# Rocketometer2148_MPU9150.net
KiCad netlist of a schematic drawn in EAGLE
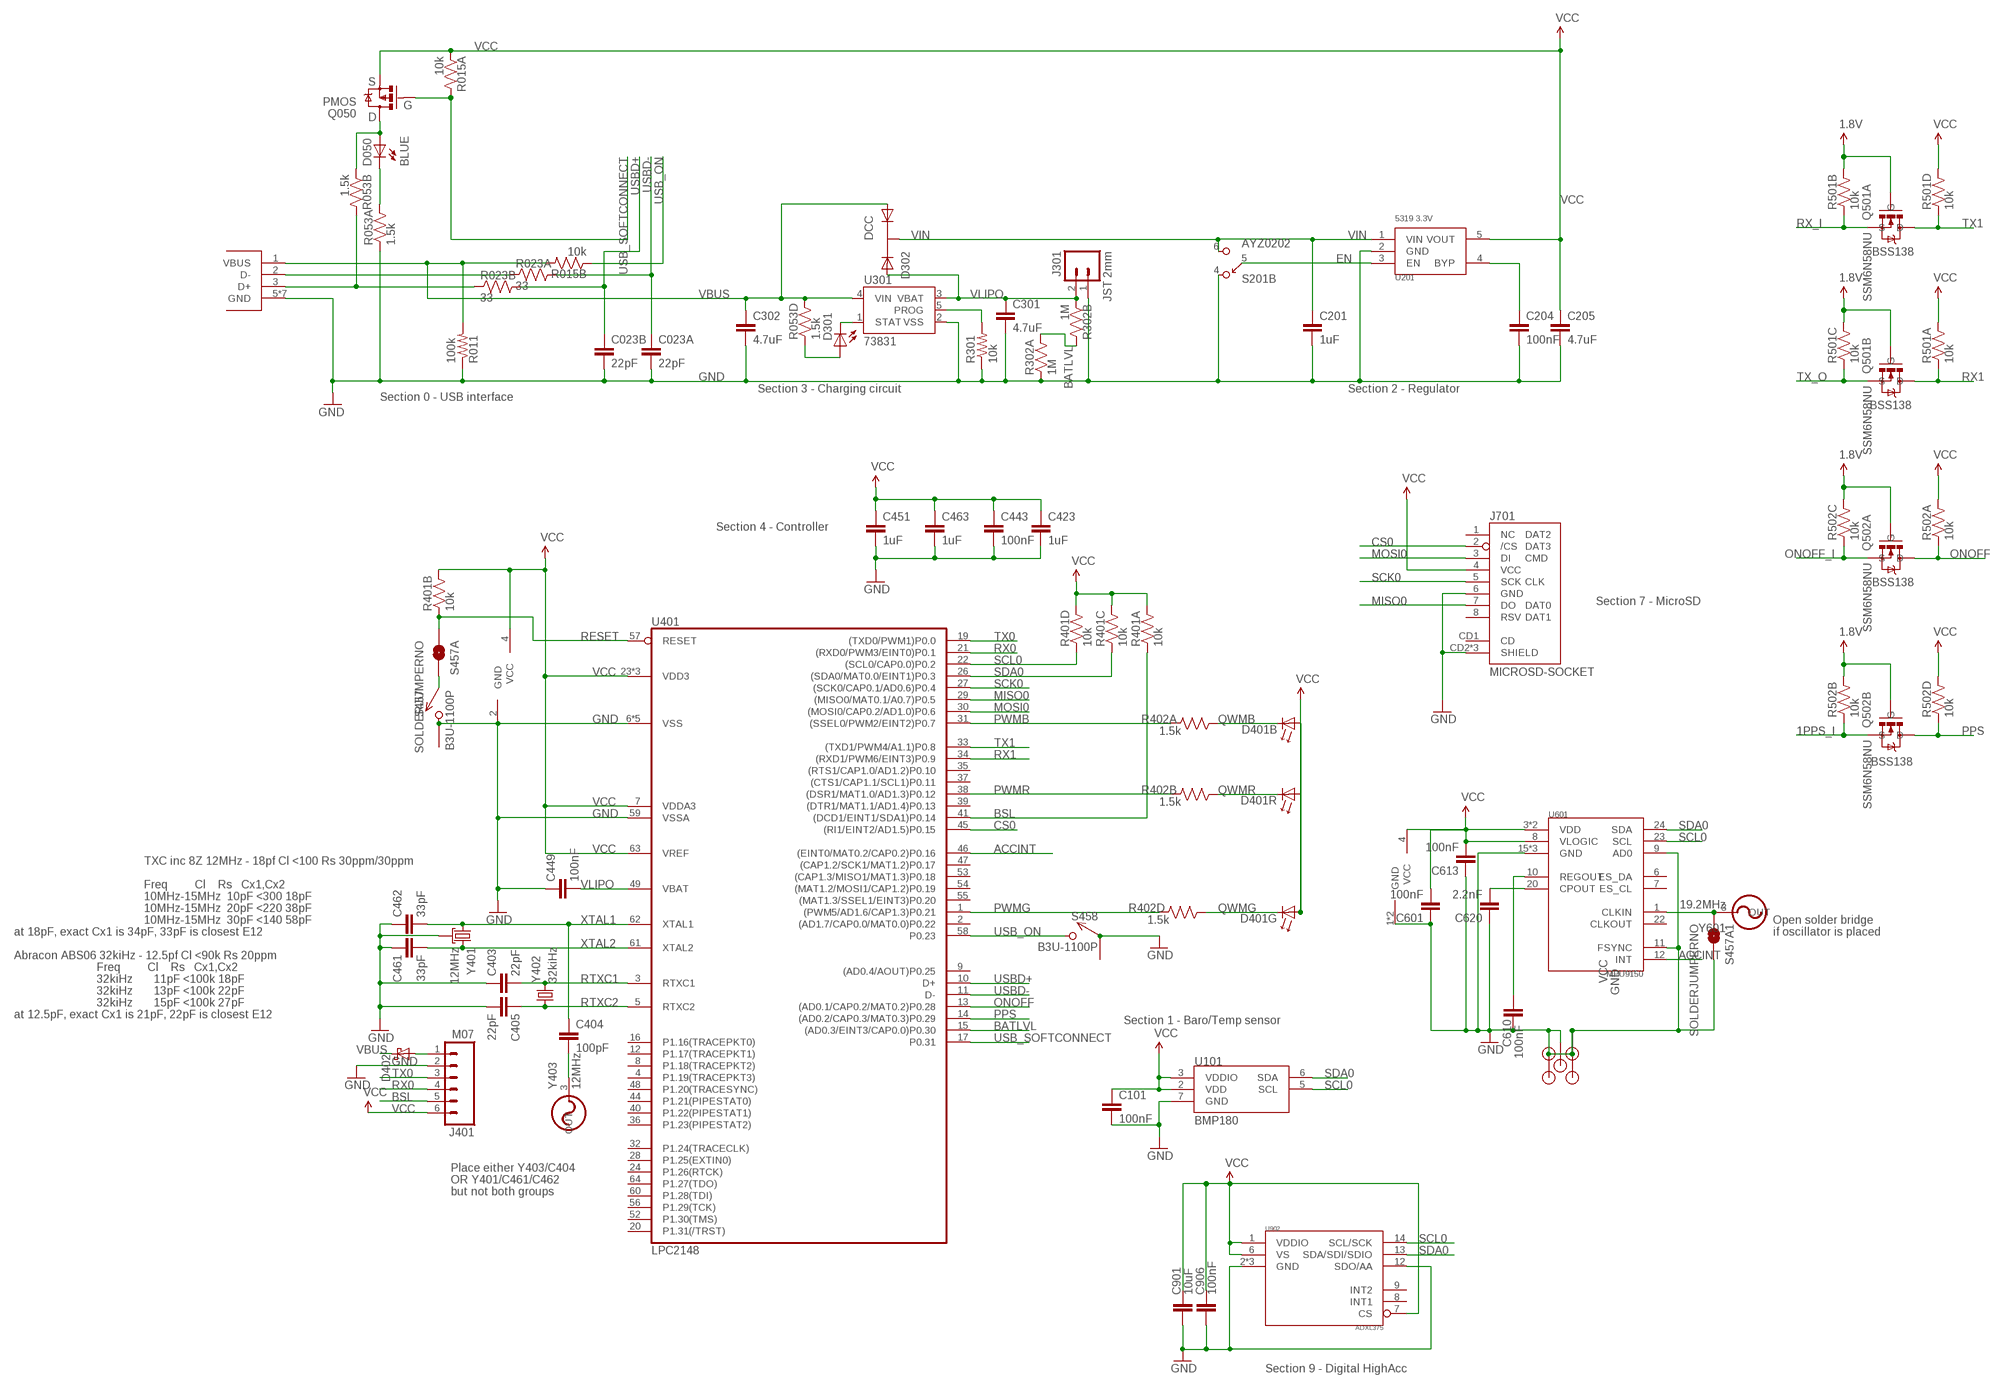
[diagram p0: schematic, sheet 1, part 1 of 2]
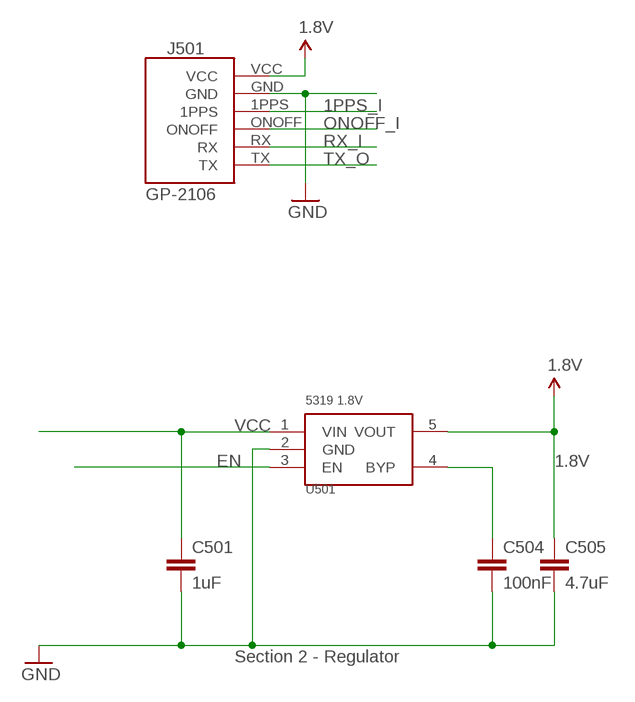
[diagram p1: schematic, sheet 1, part 2 of 2]

(export (version "E")
  (design (tool "Eeschema 10.0.6"))
  (components
    (comp (ref "C023")
      (value "22pF")
      (footprint "eagle-import:CKCM25")
      (fields (field (name "DIGIKEY") "445-1860-1-ND"))
      (libsource (lib "eagle-import") (part "CKCM25"))
    )
    (comp (ref "C101")
      (value "100nF")
      (footprint "eagle-import:0402-CAP")
      (libsource (lib "eagle-import") (part "CAP0402-CAP"))
    )
    (comp (ref "C201")
      (value "1uF")
      (footprint "eagle-import:0402-CAP")
      (libsource (lib "eagle-import") (part "CAP0402-CAP"))
    )
    (comp (ref "C204")
      (value "100nF")
      (footprint "eagle-import:0402-CAP")
      (libsource (lib "eagle-import") (part "CAP0402-CAP"))
    )
    (comp (ref "C205")
      (value "4.7uF")
      (footprint "eagle-import:0402-CAP")
      (libsource (lib "eagle-import") (part "CAP0402-CAP"))
    )
    (comp (ref "C301")
      (value "4.7uF")
      (footprint "eagle-import:0402-CAP")
      (libsource (lib "eagle-import") (part "CAP0402-CAP"))
    )
    (comp (ref "C302")
      (value "4.7uF")
      (footprint "eagle-import:0402-CAP")
      (libsource (lib "eagle-import") (part "CAP0402-CAP"))
    )
    (comp (ref "C403")
      (value "22pF")
      (footprint "eagle-import:0402-CAP")
      (libsource (lib "eagle-import") (part "CAP0402-CAP"))
    )
    (comp (ref "C404")
      (value "100pF")
      (footprint "eagle-import:0402-CAP")
      (libsource (lib "eagle-import") (part "CAP0402-CAP"))
    )
    (comp (ref "C405")
      (value "22pF")
      (footprint "eagle-import:0402-CAP")
      (libsource (lib "eagle-import") (part "CAP0402-CAP"))
    )
    (comp (ref "C423")
      (value "1uF")
      (footprint "eagle-import:0402-CAP")
      (libsource (lib "eagle-import") (part "CAP0402-CAP"))
    )
    (comp (ref "C443")
      (value "100nF")
      (footprint "eagle-import:0402-CAP")
      (libsource (lib "eagle-import") (part "CAP0402-CAP"))
    )
    (comp (ref "C449")
      (value "100nF")
      (footprint "eagle-import:0402-CAP")
      (libsource (lib "eagle-import") (part "CAP0402-CAP"))
    )
    (comp (ref "C451")
      (value "1uF")
      (footprint "eagle-import:0402-CAP")
      (libsource (lib "eagle-import") (part "CAP0402-CAP"))
    )
    (comp (ref "C461")
      (value "33pF")
      (footprint "eagle-import:0402-CAP")
      (libsource (lib "eagle-import") (part "CAP0402-CAP"))
    )
    (comp (ref "C462")
      (value "33pF")
      (footprint "eagle-import:0402-CAP")
      (libsource (lib "eagle-import") (part "CAP0402-CAP"))
    )
    (comp (ref "C463")
      (value "1uF")
      (footprint "eagle-import:0402-CAP")
      (libsource (lib "eagle-import") (part "CAP0402-CAP"))
    )
    (comp (ref "C501")
      (value "1uF")
      (footprint "eagle-import:0402-CAP")
      (libsource (lib "eagle-import") (part "CAP0402-CAP"))
    )
    (comp (ref "C504")
      (value "100nF")
      (footprint "eagle-import:0402-CAP")
      (libsource (lib "eagle-import") (part "CAP0402-CAP"))
    )
    (comp (ref "C505")
      (value "4.7uF")
      (footprint "eagle-import:0402-CAP")
      (libsource (lib "eagle-import") (part "CAP0402-CAP"))
    )
    (comp (ref "C601")
      (value "100nF")
      (footprint "eagle-import:0402-CAP")
      (libsource (lib "eagle-import") (part "CAP0402-CAP"))
    )
    (comp (ref "C610")
      (value "100nF")
      (footprint "eagle-import:0402-CAP")
      (libsource (lib "eagle-import") (part "CAP0402-CAP"))
    )
    (comp (ref "C613")
      (value "100nF")
      (footprint "eagle-import:0402-CAP")
      (libsource (lib "eagle-import") (part "CAP0402-CAP"))
    )
    (comp (ref "C620")
      (value "2.2nF")
      (footprint "eagle-import:0402-CAP")
      (libsource (lib "eagle-import") (part "CAP0402-CAP"))
    )
    (comp (ref "C901")
      (value "10uF")
      (footprint "eagle-import:0603-CAP")
      (libsource (lib "eagle-import") (part "CAP0603-CAP"))
    )
    (comp (ref "C906")
      (value "100nF")
      (footprint "eagle-import:0402-CAP")
      (libsource (lib "eagle-import") (part "SparkFun-Passives_CAP0402-CAP"))
    )
    (comp (ref "D050")
      (value "BLUE")
      (footprint "eagle-import:LED-0603")
      (libsource (lib "eagle-import") (part "LED0603"))
    )
    (comp (ref "D301")
      (value "YELLOW")
      (footprint "eagle-import:LED-0603")
      (libsource (lib "eagle-import") (part "LED0603"))
    )
    (comp (ref "D302")
      (value "DCC")
      (footprint "eagle-import:SOT-23-3")
      (libsource (lib "eagle-import") (part "PMEG2005CT"))
    )
    (comp (ref "D401")
      (value "SMLP36RGB2W(R)")
      (footprint "eagle-import:SMLP36")
      (fields (field (name "DIGIKEY") "846-1097-1-ND"))
      (libsource (lib "eagle-import") (part "SMLP36RGB2W(R)"))
    )
    (comp (ref "D402")
      (value "DIODE_SCHOTTKY")
      (footprint "eagle-import:D0603")
      (libsource (lib "eagle-import") (part "DIODE_SCHOTTKY"))
    )
    (comp (ref "J001")
      (value "USB_MICROB_JSTGCT")
      (footprint "eagle-import:USB_MICROB_3075")
      (libsource (lib "eagle-import") (part "USB_MICROB_JSTGCT"))
    )
    (comp (ref "J301")
      (value "JST 2mm")
      (footprint "eagle-import:JST-2-SMD")
      (libsource (lib "eagle-import") (part "M02-JST-2MM-SMT"))
    )
    (comp (ref "J401")
      (value "M07")
      (footprint "eagle-import:1X06")
      (libsource (lib "eagle-import") (part "M06SIP"))
    )
    (comp (ref "J501")
      (value "GP-2106")
      (footprint "eagle-import:GP-2106")
      (libsource (lib "eagle-import") (part "GP-2106"))
    )
    (comp (ref "J701")
      (value "MICROSD-SOCKET")
      (footprint "eagle-import:MICROSD-SOCKET-PP")
      (libsource (lib "eagle-import") (part "MICROSD-SOCKET"))
    )
    (comp (ref "JP1")
      (value "STANDOFF")
      (footprint "eagle-import:STANDOFF")
      (libsource (lib "eagle-import") (part "STANDOFF"))
    )
    (comp (ref "JP2")
      (value "STANDOFF")
      (footprint "eagle-import:STANDOFF")
      (libsource (lib "eagle-import") (part "STANDOFF"))
    )
    (comp (ref "JP3")
      (value "STANDOFF")
      (footprint "eagle-import:STANDOFF")
      (libsource (lib "eagle-import") (part "STANDOFF"))
    )
    (comp (ref "JP4")
      (value "STANDOFF")
      (footprint "eagle-import:STANDOFF")
      (libsource (lib "eagle-import") (part "STANDOFF"))
    )
    (comp (ref "JP5")
      (value "STANDOFF")
      (footprint "eagle-import:STANDOFF")
      (libsource (lib "eagle-import") (part "STANDOFF"))
    )
    (comp (ref "Q050")
      (value "PMOS")
      (footprint "eagle-import:SOT23-3")
      (libsource (lib "eagle-import") (part "MOSFET-PCHANNELSMD"))
    )
    (comp (ref "Q501")
      (value "SSM6N58NU")
      (footprint "eagle-import:UDFN6")
      (libsource (lib "eagle-import") (part "SSM6N58NU"))
    )
    (comp (ref "Q502")
      (value "SSM6N58NU")
      (footprint "eagle-import:UDFN6")
      (libsource (lib "eagle-import") (part "SSM6N58NU"))
    )
    (comp (ref "R011")
      (value "100k")
      (footprint "eagle-import:0402-RES")
      (libsource (lib "eagle-import") (part "RESISTOR0402-RES"))
    )
    (comp (ref "R015")
      (value "10k")
      (footprint "eagle-import:CRA02")
      (fields (field (name "DIGIKEY") "Y5103CT-ND"))
      (libsource (lib "eagle-import") (part "RP2EXB24V"))
    )
    (comp (ref "R023")
      (value "33")
      (footprint "eagle-import:CRA02")
      (libsource (lib "eagle-import") (part "RP2EXB24V"))
    )
    (comp (ref "R053")
      (value "1.5k")
      (footprint "eagle-import:CRA04")
      (fields (field (name "DIGIKEY") "CRA4S81.5KCT-ND"))
      (libsource (lib "eagle-import") (part "RP404"))
    )
    (comp (ref "R301")
      (value "10k")
      (footprint "eagle-import:0402-RES")
      (libsource (lib "eagle-import") (part "RESISTOR0402-RES"))
    )
    (comp (ref "R302")
      (value "1M")
      (footprint "eagle-import:CRA02")
      (libsource (lib "eagle-import") (part "RP2EXB24V"))
    )
    (comp (ref "R401")
      (value "10k")
      (footprint "eagle-import:CRA04")
      (fields (field (name "DIGIKEY") "CRA4S810KCT-ND"))
      (libsource (lib "eagle-import") (part "RP404"))
    )
    (comp (ref "R402")
      (value "1.5k")
      (footprint "eagle-import:CRA04")
      (fields (field (name "DIGIKEY") "CRA4S81.5KCT-ND"))
      (libsource (lib "eagle-import") (part "RP404"))
    )
    (comp (ref "R501")
      (value "10k")
      (footprint "eagle-import:CRA04")
      (fields (field (name "DIGIKEY") "CRA4S810KCT-ND"))
      (libsource (lib "eagle-import") (part "RP404"))
    )
    (comp (ref "R502")
      (value "10k")
      (footprint "eagle-import:CRA04")
      (fields (field (name "DIGIKEY") "CRA4S810KCT-ND"))
      (libsource (lib "eagle-import") (part "RP404"))
    )
    (comp (ref "S201")
      (value "AYZ0202")
      (footprint "eagle-import:AYZ0202")
      (libsource (lib "eagle-import") (part "AYZ0202"))
    )
    (comp (ref "S457")
      (value "B3U-1100P")
      (footprint "eagle-import:B3U-1100P")
      (fields (field (name "DIGIKEY") "SW1021CT-ND"))
      (libsource (lib "eagle-import") (part "B3U-1100P"))
    )
    (comp (ref "S457A")
      (value "SOLDERJUMPERNO")
      (footprint "eagle-import:SJ_2S-NO")
      (libsource (lib "eagle-import") (part "SOLDERJUMPERNO"))
    )
    (comp (ref "S457A1")
      (value "SOLDERJUMPERNO")
      (footprint "eagle-import:SJ_2S-NO")
      (libsource (lib "eagle-import") (part "SOLDERJUMPERNO"))
    )
    (comp (ref "S458")
      (value "B3U-1100P")
      (footprint "eagle-import:B3U-1100P")
      (fields (field (name "DIGIKEY") "SW1021CT-ND"))
      (libsource (lib "eagle-import") (part "B3U-1100P"))
    )
    (comp (ref "U101")
      (value "BMP180")
      (footprint "eagle-import:BMP180")
      (libsource (lib "eagle-import") (part "BMP180"))
    )
    (comp (ref "U201")
      (value "5319 3.3V")
      (footprint "eagle-import:SOT-23-5")
      (libsource (lib "eagle-import") (part "MIC5319D5"))
    )
    (comp (ref "U301")
      (value "73831")
      (footprint "eagle-import:SOT23-5")
      (libsource (lib "eagle-import") (part "MCP73831"))
    )
    (comp (ref "U401")
      (value "LPC2148")
      (footprint "eagle-import:LQFP64")
      (libsource (lib "eagle-import") (part "LPC2148"))
    )
    (comp (ref "U501")
      (value "5319 1.8V")
      (footprint "eagle-import:SOT-23-5")
      (libsource (lib "eagle-import") (part "MIC5319D5"))
    )
    (comp (ref "U601")
      (value "MPU9150")
      (footprint "eagle-import:LLGA24")
      (libsource (lib "eagle-import") (part "MPU9150"))
    )
    (comp (ref "U902")
      (value "ADXL375")
      (footprint "eagle-import:ADXL375")
      (libsource (lib "eagle-import") (part "ADXL375"))
    )
    (comp (ref "Y401")
      (value "12MHz")
      (footprint "eagle-import:CRYSTAL_SMD_2MM_2_5MM")
      (libsource (lib "eagle-import") (part "CX2520"))
    )
    (comp (ref "Y402")
      (value "32kiHz")
      (footprint "eagle-import:ABS06")
      (libsource (lib "eagle-import") (part "ABS06"))
    )
    (comp (ref "Y403")
      (value "12MHz")
      (footprint "eagle-import:CRYSTAL_SMD_5MM_3_2MM")
      (fields (field (name "DIGIKEY") "631-1068-1-ND"))
      (libsource (lib "eagle-import") (part "OSCILLATORE35MT"))
    )
    (comp (ref "Y601")
      (value "19.2MHz")
      (footprint "eagle-import:CRYSTAL_SMD_2MM_2_5MM")
      (libsource (lib "eagle-import") (part "OSCILLATORASDMB"))
    )
  )
  (nets
    (net (code "1") (name "/1PPS_I") (class "Default")
      (node (ref "J501") (pin "1PPS") (pinfunction "1PPS_1PPS") (pintype "bidirectional"))
      (node (ref "Q502") (pin "4") (pinfunction "S_4") (pintype "passive"))
      (node (ref "R502") (pin "2") (pinfunction "1_2") (pintype "passive"))
    )
    (net (code "2") (name "/ACCINT") (class "Default")
      (node (ref "U401") (pin "46") (pinfunction "(EINT0/MAT0.2/CAP0.2)P0.16_46") (pintype "bidirectional"))
      (node (ref "U601") (pin "12") (pinfunction "INT_12") (pintype "bidirectional"))
    )
    (net (code "3") (name "/BATLVL") (class "Default")
      (node (ref "R302") (pin "3") (pinfunction "2_3") (pintype "passive"))
      (node (ref "R302") (pin "4") (pinfunction "2_4") (pintype "passive"))
      (node (ref "U401") (pin "15") (pinfunction "(AD0.3/EINT3/CAP0.0)P0.30_15") (pintype "bidirectional"))
    )
    (net (code "4") (name "/BSL") (class "Default")
      (node (ref "J401") (pin "5") (pinfunction "5_5") (pintype "passive"))
      (node (ref "R401") (pin "1") (pinfunction "1_1") (pintype "passive"))
      (node (ref "U401") (pin "41") (pinfunction "(DCD1/EINT1/SDA1)P0.14_41") (pintype "bidirectional"))
    )
    (net (code "5") (name "/CS0") (class "Default")
      (node (ref "J701") (pin "2") (pinfunction "/CS_2") (pintype "bidirectional"))
      (node (ref "U401") (pin "45") (pinfunction "(RI1/EINT2/AD1.5)P0.15_45") (pintype "bidirectional"))
    )
    (net (code "6") (name "/EN") (class "Default")
      (node (ref "S201") (pin "5") (pinfunction "P$3_5") (pintype "bidirectional"))
      (node (ref "U201") (pin "3") (pinfunction "EN_3") (pintype "bidirectional"))
      (node (ref "U501") (pin "3") (pinfunction "EN_3") (pintype "bidirectional"))
    )
    (net (code "7") (name "/MISO0") (class "Default")
      (node (ref "J701") (pin "7") (pinfunction "DO_7") (pintype "bidirectional"))
      (node (ref "U401") (pin "29") (pinfunction "(MISO0/MAT0.1/A0.7)P0.5_29") (pintype "bidirectional"))
    )
    (net (code "8") (name "/MOSI0") (class "Default")
      (node (ref "J701") (pin "3") (pinfunction "DI_3") (pintype "bidirectional"))
      (node (ref "U401") (pin "30") (pinfunction "(MOSI0/CAP0.2/AD1.0)P0.6_30") (pintype "bidirectional"))
    )
    (net (code "9") (name "/ONOFF") (class "Default")
      (node (ref "Q502") (pin "6") (pinfunction "D_6") (pintype "passive"))
      (node (ref "R502") (pin "1") (pinfunction "1_1") (pintype "passive"))
      (node (ref "U401") (pin "13") (pinfunction "(AD0.1/CAP0.2/MAT0.2)P0.28_13") (pintype "bidirectional"))
    )
    (net (code "10") (name "/ONOFF_I") (class "Default")
      (node (ref "J501") (pin "ONOFF") (pinfunction "ONOFF_ONOFF") (pintype "bidirectional"))
      (node (ref "Q502") (pin "1") (pinfunction "S_1") (pintype "passive"))
      (node (ref "R502") (pin "3") (pinfunction "1_3") (pintype "passive"))
    )
    (net (code "11") (name "/PPS") (class "Default")
      (node (ref "Q502") (pin "3") (pinfunction "D_3") (pintype "passive"))
      (node (ref "R502") (pin "4") (pinfunction "1_4") (pintype "passive"))
      (node (ref "U401") (pin "14") (pinfunction "(AD0.2/CAP0.3/MAT0.3)P0.29_14") (pintype "bidirectional"))
    )
    (net (code "12") (name "/PWMB") (class "Default")
      (node (ref "R402") (pin "8") (pinfunction "2_8") (pintype "passive"))
      (node (ref "U401") (pin "31") (pinfunction "(SSEL0/PWM2/EINT2)P0.7_31") (pintype "bidirectional"))
    )
    (net (code "13") (name "/PWMG") (class "Default")
      (node (ref "R402") (pin "5") (pinfunction "2_5") (pintype "passive"))
      (node (ref "U401") (pin "1") (pinfunction "(PWM5/AD1.6/CAP1.3)P0.21_1") (pintype "bidirectional"))
    )
    (net (code "14") (name "/PWMR") (class "Default")
      (node (ref "R402") (pin "7") (pinfunction "2_7") (pintype "passive"))
      (node (ref "U401") (pin "38") (pinfunction "(DSR1/MAT1.0/AD1.3)P0.12_38") (pintype "bidirectional"))
    )
    (net (code "15") (name "/QWMB") (class "Default")
      (node (ref "D401") (pin "1") (pinfunction "C_1") (pintype "passive"))
      (node (ref "R402") (pin "1") (pinfunction "1_1") (pintype "passive"))
    )
    (net (code "16") (name "/QWMG") (class "Default")
      (node (ref "D401") (pin "5") (pinfunction "C_5") (pintype "passive"))
      (node (ref "R402") (pin "4") (pinfunction "1_4") (pintype "passive"))
    )
    (net (code "17") (name "/QWMR") (class "Default")
      (node (ref "D401") (pin "3") (pinfunction "C_3") (pintype "passive"))
      (node (ref "R402") (pin "2") (pinfunction "1_2") (pintype "passive"))
    )
    (net (code "18") (name "/RESET") (class "Default")
      (node (ref "R401") (pin "2") (pinfunction "1_2") (pintype "passive"))
      (node (ref "S457A") (pin "1") (pinfunction "1_1") (pintype "passive"))
      (node (ref "U401") (pin "57") (pinfunction "RESET_57") (pintype "input"))
    )
    (net (code "19") (name "/RTXC1") (class "Default")
      (node (ref "C403") (pin "2") (pinfunction "2_2") (pintype "passive"))
      (node (ref "U401") (pin "3") (pinfunction "RTXC1_3") (pintype "input"))
      (node (ref "Y402") (pin "2") (pinfunction "2_2") (pintype "passive"))
    )
    (net (code "20") (name "/RTXC2") (class "Default")
      (node (ref "C405") (pin "1") (pinfunction "1_1") (pintype "passive"))
      (node (ref "U401") (pin "5") (pinfunction "RTXC2_5") (pintype "output"))
      (node (ref "Y402") (pin "1") (pinfunction "1_1") (pintype "passive"))
    )
    (net (code "21") (name "/RX0") (class "Default")
      (node (ref "J401") (pin "4") (pinfunction "4_4") (pintype "passive"))
      (node (ref "U401") (pin "21") (pinfunction "(RXD0/PWM3/EINT0)P0.1_21") (pintype "bidirectional"))
    )
    (net (code "22") (name "/RX1") (class "Default")
      (node (ref "Q501") (pin "3") (pinfunction "D_3") (pintype "passive"))
      (node (ref "R501") (pin "1") (pinfunction "1_1") (pintype "passive"))
      (node (ref "U401") (pin "34") (pinfunction "(RXD1/PWM6/EINT3)P0.9_34") (pintype "bidirectional"))
    )
    (net (code "23") (name "/RX_I") (class "Default")
      (node (ref "J501") (pin "RX") (pinfunction "RX_RX") (pintype "bidirectional"))
      (node (ref "Q501") (pin "1") (pinfunction "S_1") (pintype "passive"))
      (node (ref "R501") (pin "2") (pinfunction "1_2") (pintype "passive"))
    )
    (net (code "24") (name "/SCK0") (class "Default")
      (node (ref "J701") (pin "5") (pinfunction "SCK_5") (pintype "bidirectional"))
      (node (ref "U401") (pin "27") (pinfunction "(SCK0/CAP0.1/AD0.6)P0.4_27") (pintype "bidirectional"))
    )
    (net (code "25") (name "/SCL0") (class "Default")
      (node (ref "R401") (pin "4") (pinfunction "1_4") (pintype "passive"))
      (node (ref "U101") (pin "5") (pinfunction "SCL_5") (pintype "input"))
      (node (ref "U401") (pin "22") (pinfunction "(SCL0/CAP0.0)P0.2_22") (pintype "bidirectional"))
      (node (ref "U601") (pin "23") (pinfunction "SCL_23") (pintype "bidirectional"))
      (node (ref "U902") (pin "14") (pinfunction "SCL/SCK_14") (pintype "input"))
    )
    (net (code "26") (name "/SDA0") (class "Default")
      (node (ref "R401") (pin "3") (pinfunction "1_3") (pintype "passive"))
      (node (ref "U101") (pin "6") (pinfunction "SDA_6") (pintype "bidirectional"))
      (node (ref "U401") (pin "26") (pinfunction "(SDA0/MAT0.0/EINT1)P0.3_26") (pintype "bidirectional"))
      (node (ref "U601") (pin "24") (pinfunction "SDA_24") (pintype "bidirectional"))
      (node (ref "U902") (pin "13") (pinfunction "SDA/SDI/SDIO_13") (pintype "bidirectional"))
    )
    (net (code "27") (name "/TX0") (class "Default")
      (node (ref "J401") (pin "3") (pinfunction "3_3") (pintype "passive"))
      (node (ref "U401") (pin "19") (pinfunction "(TXD0/PWM1)P0.0_19") (pintype "bidirectional"))
    )
    (net (code "28") (name "/TX1") (class "Default")
      (node (ref "Q501") (pin "6") (pinfunction "D_6") (pintype "passive"))
      (node (ref "R501") (pin "4") (pinfunction "1_4") (pintype "passive"))
      (node (ref "U401") (pin "33") (pinfunction "(TXD1/PWM4/A1.1)P0.8_33") (pintype "bidirectional"))
    )
    (net (code "29") (name "/TX_O") (class "Default")
      (node (ref "J501") (pin "TX") (pinfunction "TX_TX") (pintype "bidirectional"))
      (node (ref "Q501") (pin "4") (pinfunction "S_4") (pintype "passive"))
      (node (ref "R501") (pin "3") (pinfunction "1_3") (pintype "passive"))
    )
    (net (code "30") (name "/USBD+") (class "Default")
      (node (ref "C023") (pin "2") (pinfunction "1_2") (pintype "passive"))
      (node (ref "R023") (pin "3") (pinfunction "2_3") (pintype "passive"))
      (node (ref "U401") (pin "10") (pinfunction "D+_10") (pintype "bidirectional"))
    )
    (net (code "31") (name "/USBD-") (class "Default")
      (node (ref "C023") (pin "1") (pinfunction "1_1") (pintype "passive"))
      (node (ref "R023") (pin "4") (pinfunction "2_4") (pintype "passive"))
      (node (ref "U401") (pin "11") (pinfunction "D-_11") (pintype "bidirectional"))
    )
    (net (code "32") (name "/USB_ON") (class "Default")
      (node (ref "R015") (pin "2") (pinfunction "1_2") (pintype "passive"))
      (node (ref "S458") (pin "P$2") (pinfunction "2_P$2") (pintype "bidirectional"))
      (node (ref "U401") (pin "58") (pinfunction "P0.23_58") (pintype "bidirectional"))
    )
    (net (code "33") (name "/USB_SOFTCONNECT") (class "Default")
      (node (ref "Q050") (pin "1") (pinfunction "G_1") (pintype "passive"))
      (node (ref "R015") (pin "4") (pinfunction "2_4") (pintype "passive"))
      (node (ref "U401") (pin "17") (pinfunction "P0.31_17") (pintype "output"))
    )
    (net (code "34") (name "/VBUS") (class "Default")
      (node (ref "C302") (pin "1") (pinfunction "1_1") (pintype "passive"))
      (node (ref "D302") (pin "1") (pinfunction "A1_1") (pintype "passive"))
      (node (ref "D402") (pin "C") (pinfunction "K_C") (pintype "passive"))
      (node (ref "J001") (pin "1") (pinfunction "VBUS_1") (pintype "bidirectional"))
      (node (ref "R011") (pin "2") (pinfunction "2_2") (pintype "passive"))
      (node (ref "R015") (pin "3") (pinfunction "2_3") (pintype "passive"))
      (node (ref "R053") (pin "5") (pinfunction "2_5") (pintype "passive"))
      (node (ref "U301") (pin "4") (pinfunction "VIN_4") (pintype "power_in"))
    )
    (net (code "35") (name "/VIN") (class "Default")
      (node (ref "C201") (pin "1") (pinfunction "1_1") (pintype "passive"))
      (node (ref "D302") (pin "3") (pinfunction "K_3") (pintype "passive"))
      (node (ref "S201") (pin "6") (pinfunction "P$2_6") (pintype "bidirectional"))
      (node (ref "U201") (pin "1") (pinfunction "VIN_1") (pintype "bidirectional"))
    )
    (net (code "36") (name "/VLIPO") (class "Default")
      (node (ref "C301") (pin "1") (pinfunction "1_1") (pintype "passive"))
      (node (ref "C449") (pin "2") (pinfunction "2_2") (pintype "passive"))
      (node (ref "D302") (pin "2") (pinfunction "A2_2") (pintype "passive"))
      (node (ref "J301") (pin "2") (pinfunction "2_2") (pintype "passive"))
      (node (ref "R302") (pin "2") (pinfunction "1_2") (pintype "passive"))
      (node (ref "U301") (pin "3") (pinfunction "VBAT_3") (pintype "power_in"))
      (node (ref "U401") (pin "49") (pinfunction "VBAT_49") (pintype "power_in"))
    )
    (net (code "37") (name "/XTAL1") (class "Default")
      (node (ref "C404") (pin "1") (pinfunction "1_1") (pintype "passive"))
      (node (ref "C462") (pin "2") (pinfunction "2_2") (pintype "passive"))
      (node (ref "U401") (pin "62") (pinfunction "XTAL1_62") (pintype "input"))
      (node (ref "Y401") (pin "1") (pinfunction "1_1") (pintype "passive"))
    )
    (net (code "38") (name "/XTAL2") (class "Default")
      (node (ref "C461") (pin "2") (pinfunction "2_2") (pintype "passive"))
      (node (ref "U401") (pin "61") (pinfunction "XTAL2_61") (pintype "output"))
      (node (ref "Y401") (pin "3") (pinfunction "2_3") (pintype "passive"))
    )
    (net (code "39") (name "1.8V") (class "Default")
      (node (ref "C505") (pin "1") (pinfunction "1_1") (pintype "passive"))
      (node (ref "J501") (pin "VCC") (pinfunction "VCC_VCC") (pintype "bidirectional"))
      (node (ref "Q501") (pin "2") (pinfunction "G_2") (pintype "passive"))
      (node (ref "Q501") (pin "5") (pinfunction "G_5") (pintype "passive"))
      (node (ref "Q502") (pin "2") (pinfunction "G_2") (pintype "passive"))
      (node (ref "Q502") (pin "5") (pinfunction "G_5") (pintype "passive"))
      (node (ref "R501") (pin "6") (pinfunction "2_6") (pintype "passive"))
      (node (ref "R501") (pin "7") (pinfunction "2_7") (pintype "passive"))
      (node (ref "R502") (pin "6") (pinfunction "2_6") (pintype "passive"))
      (node (ref "R502") (pin "7") (pinfunction "2_7") (pintype "passive"))
      (node (ref "U501") (pin "5") (pinfunction "VOUT_5") (pintype "bidirectional"))
    )
    (net (code "40") (name "GND") (class "Default")
      (node (ref "C023") (pin "3") (pinfunction "2_3") (pintype "passive"))
      (node (ref "C023") (pin "4") (pinfunction "2_4") (pintype "passive"))
      (node (ref "C101") (pin "2") (pinfunction "2_2") (pintype "passive"))
      (node (ref "C201") (pin "2") (pinfunction "2_2") (pintype "passive"))
      (node (ref "C204") (pin "2") (pinfunction "2_2") (pintype "passive"))
      (node (ref "C205") (pin "2") (pinfunction "2_2") (pintype "passive"))
      (node (ref "C301") (pin "2") (pinfunction "2_2") (pintype "passive"))
      (node (ref "C302") (pin "2") (pinfunction "2_2") (pintype "passive"))
      (node (ref "C403") (pin "1") (pinfunction "1_1") (pintype "passive"))
      (node (ref "C405") (pin "2") (pinfunction "2_2") (pintype "passive"))
      (node (ref "C423") (pin "2") (pinfunction "2_2") (pintype "passive"))
      (node (ref "C443") (pin "2") (pinfunction "2_2") (pintype "passive"))
      (node (ref "C449") (pin "1") (pinfunction "1_1") (pintype "passive"))
      (node (ref "C451") (pin "2") (pinfunction "2_2") (pintype "passive"))
      (node (ref "C461") (pin "1") (pinfunction "1_1") (pintype "passive"))
      (node (ref "C462") (pin "1") (pinfunction "1_1") (pintype "passive"))
      (node (ref "C463") (pin "2") (pinfunction "2_2") (pintype "passive"))
      (node (ref "C501") (pin "2") (pinfunction "2_2") (pintype "passive"))
      (node (ref "C504") (pin "2") (pinfunction "2_2") (pintype "passive"))
      (node (ref "C505") (pin "2") (pinfunction "2_2") (pintype "passive"))
      (node (ref "C601") (pin "1") (pinfunction "1_1") (pintype "passive"))
      (node (ref "C610") (pin "2") (pinfunction "2_2") (pintype "passive"))
      (node (ref "C613") (pin "1") (pinfunction "1_1") (pintype "passive"))
      (node (ref "C620") (pin "1") (pinfunction "1_1") (pintype "passive"))
      (node (ref "C901") (pin "2") (pinfunction "2_2") (pintype "passive"))
      (node (ref "C906") (pin "2") (pinfunction "2_2") (pintype "passive"))
      (node (ref "J001") (pin "5") (pinfunction "GND_5") (pintype "bidirectional"))
      (node (ref "J001") (pin "P$1") (pinfunction "GND_P$1") (pintype "bidirectional"))
      (node (ref "J001") (pin "P$10") (pinfunction "GND_P$10") (pintype "bidirectional"))
      (node (ref "J001") (pin "P$2") (pinfunction "GND_P$2") (pintype "bidirectional"))
      (node (ref "J001") (pin "P$3") (pinfunction "GND_P$3") (pintype "bidirectional"))
      (node (ref "J001") (pin "P$4") (pinfunction "GND_P$4") (pintype "bidirectional"))
      (node (ref "J001") (pin "P$8") (pinfunction "GND_P$8") (pintype "bidirectional"))
      (node (ref "J301") (pin "1") (pinfunction "1_1") (pintype "passive"))
      (node (ref "J401") (pin "2") (pinfunction "2_2") (pintype "passive"))
      (node (ref "J501") (pin "GND") (pinfunction "GND_GND") (pintype "bidirectional"))
      (node (ref "J701") (pin "6") (pinfunction "GND_6") (pintype "bidirectional"))
      (node (ref "J701") (pin "CD2") (pinfunction "SHIELD_CD2") (pintype "bidirectional"))
      (node (ref "J701") (pin "GND1") (pinfunction "SHIELD_GND1") (pintype "bidirectional"))
      (node (ref "J701") (pin "GND3") (pinfunction "SHIELD_GND3") (pintype "bidirectional"))
      (node (ref "JP1") (pin "P$1") (pinfunction "P$1_P$1") (pintype "bidirectional"))
      (node (ref "JP2") (pin "P$1") (pinfunction "P$1_P$1") (pintype "bidirectional"))
      (node (ref "JP3") (pin "P$1") (pinfunction "P$1_P$1") (pintype "bidirectional"))
      (node (ref "JP4") (pin "P$1") (pinfunction "P$1_P$1") (pintype "bidirectional"))
      (node (ref "JP5") (pin "P$1") (pinfunction "P$1_P$1") (pintype "bidirectional"))
      (node (ref "R011") (pin "1") (pinfunction "1_1") (pintype "passive"))
      (node (ref "R053") (pin "1") (pinfunction "1_1") (pintype "passive"))
      (node (ref "R301") (pin "1") (pinfunction "1_1") (pintype "passive"))
      (node (ref "R302") (pin "1") (pinfunction "1_1") (pintype "passive"))
      (node (ref "S201") (pin "4") (pinfunction "P$1_4") (pintype "bidirectional"))
      (node (ref "S457") (pin "P$2") (pinfunction "2_P$2") (pintype "bidirectional"))
      (node (ref "S457") (pin "P$3") (pinfunction "1_P$3") (pintype "bidirectional"))
      (node (ref "S457A1") (pin "2") (pinfunction "2_2") (pintype "passive"))
      (node (ref "S458") (pin "P$1") (pinfunction "1_P$1") (pintype "bidirectional"))
      (node (ref "S458") (pin "P$3") (pinfunction "1_P$3") (pintype "bidirectional"))
      (node (ref "U101") (pin "7") (pinfunction "GND_7") (pintype "power_in"))
      (node (ref "U201") (pin "2") (pinfunction "GND_2") (pintype "bidirectional"))
      (node (ref "U301") (pin "2") (pinfunction "VSS_2") (pintype "power_in"))
      (node (ref "U401") (pin "18") (pinfunction "VSS_18") (pintype "power_in"))
      (node (ref "U401") (pin "25") (pinfunction "VSS_25") (pintype "power_in"))
      (node (ref "U401") (pin "42") (pinfunction "VSS_42") (pintype "power_in"))
      (node (ref "U401") (pin "50") (pinfunction "VSS_50") (pintype "power_in"))
      (node (ref "U401") (pin "59") (pinfunction "VSSA_59") (pintype "power_in"))
      (node (ref "U401") (pin "6") (pinfunction "VSS_6") (pintype "power_in"))
      (node (ref "U501") (pin "2") (pinfunction "GND_2") (pintype "bidirectional"))
      (node (ref "U601") (pin "11") (pinfunction "FSYNC_11") (pintype "bidirectional"))
      (node (ref "U601") (pin "15") (pinfunction "GND_15") (pintype "bidirectional"))
      (node (ref "U601") (pin "17") (pinfunction "GND_17") (pintype "bidirectional"))
      (node (ref "U601") (pin "18") (pinfunction "GND_18") (pintype "bidirectional"))
      (node (ref "U601") (pin "9") (pinfunction "AD0_9") (pintype "bidirectional"))
      (node (ref "U902") (pin "12") (pinfunction "SDO/AA_12") (pintype "bidirectional"))
      (node (ref "U902") (pin "2") (pinfunction "GND_2") (pintype "power_in"))
      (node (ref "U902") (pin "4") (pinfunction "GND_4") (pintype "power_in"))
      (node (ref "U902") (pin "5") (pinfunction "GND_5") (pintype "power_in"))
      (node (ref "Y401") (pin "2") (pinfunction "GND_2") (pintype "passive"))
      (node (ref "Y401") (pin "4") (pinfunction "GND_4") (pintype "passive"))
      (node (ref "Y403") (pin "2") (pinfunction "GND_2") (pintype "bidirectional"))
      (node (ref "Y601") (pin "1") (pinfunction "GND_1") (pintype "bidirectional"))
      (node (ref "Y601") (pin "2") (pinfunction "GND_2") (pintype "bidirectional"))
    )
    (net (code "41") (name "Net-(D402-PadA)") (class "Default")
      (node (ref "D402") (pin "A") (pinfunction "A_A") (pintype "passive"))
      (node (ref "J401") (pin "1") (pinfunction "1_1") (pintype "passive"))
    )
    (net (code "42") (name "Net-(J001-D+)") (class "Default")
      (node (ref "J001") (pin "3") (pinfunction "D+_3") (pintype "bidirectional"))
      (node (ref "R023") (pin "2") (pinfunction "1_2") (pintype "passive"))
      (node (ref "R053") (pin "7") (pinfunction "2_7") (pintype "passive"))
    )
    (net (code "43") (name "Net-(J001-D-)") (class "Default")
      (node (ref "J001") (pin "2") (pinfunction "D-_2") (pintype "bidirectional"))
      (node (ref "R023") (pin "1") (pinfunction "1_1") (pintype "passive"))
    )
    (net (code "44") (name "Net-(Q050-D)") (class "Default")
      (node (ref "D050") (pin "A") (pinfunction "A_A") (pintype "passive"))
      (node (ref "Q050") (pin "3") (pinfunction "D_3") (pintype "passive"))
      (node (ref "R053") (pin "2") (pinfunction "1_2") (pintype "passive"))
    )
    (net (code "45") (name "Net-(R053A-2)") (class "Default")
      (node (ref "D050") (pin "C") (pinfunction "C_C") (pintype "passive"))
      (node (ref "R053") (pin "8") (pinfunction "2_8") (pintype "passive"))
    )
    (net (code "46") (name "Net-(R053D-1)") (class "Default")
      (node (ref "D301") (pin "A") (pinfunction "A_A") (pintype "passive"))
      (node (ref "R053") (pin "4") (pinfunction "1_4") (pintype "passive"))
    )
    (net (code "47") (name "Net-(S457B-1)") (class "Default")
      (node (ref "S457") (pin "P$1") (pinfunction "1_P$1") (pintype "bidirectional"))
      (node (ref "S457A") (pin "2") (pinfunction "2_2") (pintype "passive"))
    )
    (net (code "48") (name "Net-(U201-BYP)") (class "Default")
      (node (ref "C204") (pin "1") (pinfunction "1_1") (pintype "passive"))
      (node (ref "U201") (pin "4") (pinfunction "BYP_4") (pintype "bidirectional"))
    )
    (net (code "49") (name "Net-(U301-PROG)") (class "Default")
      (node (ref "R301") (pin "2") (pinfunction "2_2") (pintype "passive"))
      (node (ref "U301") (pin "5") (pinfunction "PROG_5") (pintype "input"))
    )
    (net (code "50") (name "Net-(U301-STAT)") (class "Default")
      (node (ref "D301") (pin "C") (pinfunction "C_C") (pintype "passive"))
      (node (ref "U301") (pin "1") (pinfunction "STAT_1") (pintype "output"))
    )
    (net (code "51") (name "Net-(U501-BYP)") (class "Default")
      (node (ref "C504") (pin "1") (pinfunction "1_1") (pintype "passive"))
      (node (ref "U501") (pin "4") (pinfunction "BYP_4") (pintype "bidirectional"))
    )
    (net (code "52") (name "Net-(U601-CLKIN)") (class "Default")
      (node (ref "S457A1") (pin "1") (pinfunction "1_1") (pintype "passive"))
      (node (ref "U601") (pin "1") (pinfunction "CLKIN_1") (pintype "bidirectional"))
      (node (ref "Y601") (pin "3") (pinfunction "OUT_3") (pintype "bidirectional"))
    )
    (net (code "53") (name "Net-(U601-CPOUT)") (class "Default")
      (node (ref "C620") (pin "2") (pinfunction "2_2") (pintype "passive"))
      (node (ref "U601") (pin "20") (pinfunction "CPOUT_20") (pintype "bidirectional"))
    )
    (net (code "54") (name "Net-(U601-REGOUT)") (class "Default")
      (node (ref "C610") (pin "1") (pinfunction "1_1") (pintype "passive"))
      (node (ref "U601") (pin "10") (pinfunction "REGOUT_10") (pintype "bidirectional"))
    )
    (net (code "55") (name "Net-(Y403A-OUT)") (class "Default")
      (node (ref "C404") (pin "2") (pinfunction "2_2") (pintype "passive"))
      (node (ref "Y403") (pin "3") (pinfunction "OUT_3") (pintype "bidirectional"))
    )
    (net (code "56") (name "VCC") (class "Default")
      (node (ref "C101") (pin "1") (pinfunction "1_1") (pintype "passive"))
      (node (ref "C205") (pin "1") (pinfunction "1_1") (pintype "passive"))
      (node (ref "C423") (pin "1") (pinfunction "1_1") (pintype "passive"))
      (node (ref "C443") (pin "1") (pinfunction "1_1") (pintype "passive"))
      (node (ref "C451") (pin "1") (pinfunction "1_1") (pintype "passive"))
      (node (ref "C463") (pin "1") (pinfunction "1_1") (pintype "passive"))
      (node (ref "C501") (pin "1") (pinfunction "1_1") (pintype "passive"))
      (node (ref "C601") (pin "2") (pinfunction "2_2") (pintype "passive"))
      (node (ref "C613") (pin "2") (pinfunction "2_2") (pintype "passive"))
      (node (ref "C901") (pin "1") (pinfunction "1_1") (pintype "passive"))
      (node (ref "C906") (pin "1") (pinfunction "1_1") (pintype "passive"))
      (node (ref "D401") (pin "2") (pinfunction "A_2") (pintype "passive"))
      (node (ref "D401") (pin "4") (pinfunction "A_4") (pintype "passive"))
      (node (ref "D401") (pin "6") (pinfunction "A_6") (pintype "passive"))
      (node (ref "J401") (pin "6") (pinfunction "6_6") (pintype "passive"))
      (node (ref "J701") (pin "4") (pinfunction "VCC_4") (pintype "bidirectional"))
      (node (ref "Q050") (pin "2") (pinfunction "S_2") (pintype "passive"))
      (node (ref "R015") (pin "1") (pinfunction "1_1") (pintype "passive"))
      (node (ref "R401") (pin "5") (pinfunction "2_5") (pintype "passive"))
      (node (ref "R401") (pin "6") (pinfunction "2_6") (pintype "passive"))
      (node (ref "R401") (pin "7") (pinfunction "2_7") (pintype "passive"))
      (node (ref "R401") (pin "8") (pinfunction "2_8") (pintype "passive"))
      (node (ref "R501") (pin "5") (pinfunction "2_5") (pintype "passive"))
      (node (ref "R501") (pin "8") (pinfunction "2_8") (pintype "passive"))
      (node (ref "R502") (pin "5") (pinfunction "2_5") (pintype "passive"))
      (node (ref "R502") (pin "8") (pinfunction "2_8") (pintype "passive"))
      (node (ref "U101") (pin "2") (pinfunction "VDD_2") (pintype "power_in"))
      (node (ref "U101") (pin "3") (pinfunction "VDDIO_3") (pintype "power_in"))
      (node (ref "U201") (pin "5") (pinfunction "VOUT_5") (pintype "bidirectional"))
      (node (ref "U401") (pin "23") (pinfunction "VDD3_23") (pintype "power_in"))
      (node (ref "U401") (pin "43") (pinfunction "VDD3_43") (pintype "power_in"))
      (node (ref "U401") (pin "51") (pinfunction "VDD3_51") (pintype "power_in"))
      (node (ref "U401") (pin "63") (pinfunction "VREF_63") (pintype "input"))
      (node (ref "U401") (pin "7") (pinfunction "VDDA3_7") (pintype "power_in"))
      (node (ref "U501") (pin "1") (pinfunction "VIN_1") (pintype "bidirectional"))
      (node (ref "U601") (pin "13") (pinfunction "VDD_13") (pintype "bidirectional"))
      (node (ref "U601") (pin "3") (pinfunction "VDD_3") (pintype "bidirectional"))
      (node (ref "U601") (pin "8") (pinfunction "VLOGIC_8") (pintype "bidirectional"))
      (node (ref "U902") (pin "1") (pinfunction "VDDIO_1") (pintype "power_in"))
      (node (ref "U902") (pin "6") (pinfunction "VS_6") (pintype "power_in"))
      (node (ref "U902") (pin "7") (pinfunction "CS_7") (pintype "input"))
      (node (ref "Y403") (pin "4") (pinfunction "VCC_4") (pintype "bidirectional"))
      (node (ref "Y601") (pin "4") (pinfunction "VCC_4") (pintype "bidirectional"))
    )
    (net (code "57") (name "unconnected-(J701-CD-PadCD1)") (class "Default")
      (node (ref "J701") (pin "CD1") (pinfunction "CD_CD1") (pintype "bidirectional"))
    )
    (net (code "58") (name "unconnected-(J701-NC-Pad1)") (class "Default")
      (node (ref "J701") (pin "1") (pinfunction "NC_1") (pintype "bidirectional"))
    )
    (net (code "59") (name "unconnected-(J701-RSV-Pad8)") (class "Default")
      (node (ref "J701") (pin "8") (pinfunction "RSV_8") (pintype "bidirectional"))
    )
    (net (code "60") (name "unconnected-(U401-(AD0.4{slash}AOUT)P0.25-Pad9)") (class "Default")
      (node (ref "U401") (pin "9") (pinfunction "(AD0.4/AOUT)P0.25_9") (pintype "bidirectional"))
    )
    (net (code "61") (name "unconnected-(U401-(AD1.7{slash}CAP0.0{slash}MAT0.0)P0.22-Pad2)") (class "Default")
      (node (ref "U401") (pin "2") (pinfunction "(AD1.7/CAP0.0/MAT0.0)P0.22_2") (pintype "bidirectional"))
    )
    (net (code "62") (name "unconnected-(U401-(CAP1.2{slash}SCK1{slash}MAT1.2)P0.17-Pad47)") (class "Default")
      (node (ref "U401") (pin "47") (pinfunction "(CAP1.2/SCK1/MAT1.2)P0.17_47") (pintype "bidirectional"))
    )
    (net (code "63") (name "unconnected-(U401-(CAP1.3{slash}MISO1{slash}MAT1.3)P0.18-Pad53)") (class "Default")
      (node (ref "U401") (pin "53") (pinfunction "(CAP1.3/MISO1/MAT1.3)P0.18_53") (pintype "bidirectional"))
    )
    (net (code "64") (name "unconnected-(U401-(CTS1{slash}CAP1.1{slash}SCL1)P0.11-Pad37)") (class "Default")
      (node (ref "U401") (pin "37") (pinfunction "(CTS1/CAP1.1/SCL1)P0.11_37") (pintype "bidirectional"))
    )
    (net (code "65") (name "unconnected-(U401-(DTR1{slash}MAT1.1{slash}AD1.4)P0.13-Pad39)") (class "Default")
      (node (ref "U401") (pin "39") (pinfunction "(DTR1/MAT1.1/AD1.4)P0.13_39") (pintype "bidirectional"))
    )
    (net (code "66") (name "unconnected-(U401-(MAT1.2{slash}MOSI1{slash}CAP1.2)P0.19-Pad54)") (class "Default")
      (node (ref "U401") (pin "54") (pinfunction "(MAT1.2/MOSI1/CAP1.2)P0.19_54") (pintype "bidirectional"))
    )
    (net (code "67") (name "unconnected-(U401-(MAT1.3{slash}SSEL1{slash}EINT3)P0.20-Pad55)") (class "Default")
      (node (ref "U401") (pin "55") (pinfunction "(MAT1.3/SSEL1/EINT3)P0.20_55") (pintype "bidirectional"))
    )
    (net (code "68") (name "unconnected-(U401-(RTS1{slash}CAP1.0{slash}AD1.2)P0.10-Pad35)") (class "Default")
      (node (ref "U401") (pin "35") (pinfunction "(RTS1/CAP1.0/AD1.2)P0.10_35") (pintype "bidirectional"))
    )
    (net (code "69") (name "unconnected-(U401-P1.16(TRACEPKT0)-Pad16)") (class "Default")
      (node (ref "U401") (pin "16") (pinfunction "P1.16(TRACEPKT0)_16") (pintype "bidirectional"))
    )
    (net (code "70") (name "unconnected-(U401-P1.17(TRACEPKT1)-Pad12)") (class "Default")
      (node (ref "U401") (pin "12") (pinfunction "P1.17(TRACEPKT1)_12") (pintype "bidirectional"))
    )
    (net (code "71") (name "unconnected-(U401-P1.18(TRACEPKT2)-Pad8)") (class "Default")
      (node (ref "U401") (pin "8") (pinfunction "P1.18(TRACEPKT2)_8") (pintype "bidirectional"))
    )
    (net (code "72") (name "unconnected-(U401-P1.19(TRACEPKT3)-Pad4)") (class "Default")
      (node (ref "U401") (pin "4") (pinfunction "P1.19(TRACEPKT3)_4") (pintype "bidirectional"))
    )
    (net (code "73") (name "unconnected-(U401-P1.20(TRACESYNC)-Pad48)") (class "Default")
      (node (ref "U401") (pin "48") (pinfunction "P1.20(TRACESYNC)_48") (pintype "bidirectional"))
    )
    (net (code "74") (name "unconnected-(U401-P1.21(PIPESTAT0)-Pad44)") (class "Default")
      (node (ref "U401") (pin "44") (pinfunction "P1.21(PIPESTAT0)_44") (pintype "bidirectional"))
    )
    (net (code "75") (name "unconnected-(U401-P1.22(PIPESTAT1)-Pad40)") (class "Default")
      (node (ref "U401") (pin "40") (pinfunction "P1.22(PIPESTAT1)_40") (pintype "bidirectional"))
    )
    (net (code "76") (name "unconnected-(U401-P1.23(PIPESTAT2)-Pad36)") (class "Default")
      (node (ref "U401") (pin "36") (pinfunction "P1.23(PIPESTAT2)_36") (pintype "bidirectional"))
    )
    (net (code "77") (name "unconnected-(U401-P1.24(TRACECLK)-Pad32)") (class "Default")
      (node (ref "U401") (pin "32") (pinfunction "P1.24(TRACECLK)_32") (pintype "bidirectional"))
    )
    (net (code "78") (name "unconnected-(U401-P1.25(EXTIN0)-Pad28)") (class "Default")
      (node (ref "U401") (pin "28") (pinfunction "P1.25(EXTIN0)_28") (pintype "bidirectional"))
    )
    (net (code "79") (name "unconnected-(U401-P1.26(RTCK)-Pad24)") (class "Default")
      (node (ref "U401") (pin "24") (pinfunction "P1.26(RTCK)_24") (pintype "bidirectional"))
    )
    (net (code "80") (name "unconnected-(U401-P1.27(TDO)-Pad64)") (class "Default")
      (node (ref "U401") (pin "64") (pinfunction "P1.27(TDO)_64") (pintype "bidirectional"))
    )
    (net (code "81") (name "unconnected-(U401-P1.28(TDI)-Pad60)") (class "Default")
      (node (ref "U401") (pin "60") (pinfunction "P1.28(TDI)_60") (pintype "bidirectional"))
    )
    (net (code "82") (name "unconnected-(U401-P1.29(TCK)-Pad56)") (class "Default")
      (node (ref "U401") (pin "56") (pinfunction "P1.29(TCK)_56") (pintype "bidirectional"))
    )
    (net (code "83") (name "unconnected-(U401-P1.30(TMS)-Pad52)") (class "Default")
      (node (ref "U401") (pin "52") (pinfunction "P1.30(TMS)_52") (pintype "bidirectional"))
    )
    (net (code "84") (name "unconnected-(U401-P1.31({slash}TRST)-Pad20)") (class "Default")
      (node (ref "U401") (pin "20") (pinfunction "P1.31(/TRST)_20") (pintype "bidirectional"))
    )
    (net (code "85") (name "unconnected-(U601-CLKOUT-Pad22)") (class "Default")
      (node (ref "U601") (pin "22") (pinfunction "CLKOUT_22") (pintype "bidirectional"))
    )
    (net (code "86") (name "unconnected-(U601-ES_CL-Pad7)") (class "Default")
      (node (ref "U601") (pin "7") (pinfunction "ES_CL_7") (pintype "bidirectional"))
    )
    (net (code "87") (name "unconnected-(U601-ES_DA-Pad6)") (class "Default")
      (node (ref "U601") (pin "6") (pinfunction "ES_DA_6") (pintype "bidirectional"))
    )
    (net (code "88") (name "unconnected-(U902-INT1-Pad8)") (class "Default")
      (node (ref "U902") (pin "8") (pinfunction "INT1_8") (pintype "output"))
    )
    (net (code "89") (name "unconnected-(U902-INT2-Pad9)") (class "Default")
      (node (ref "U902") (pin "9") (pinfunction "INT2_9") (pintype "output"))
    )
  )
)
